# Sensor.net
KiCad netlist of a schematic drawn in Altium Designer
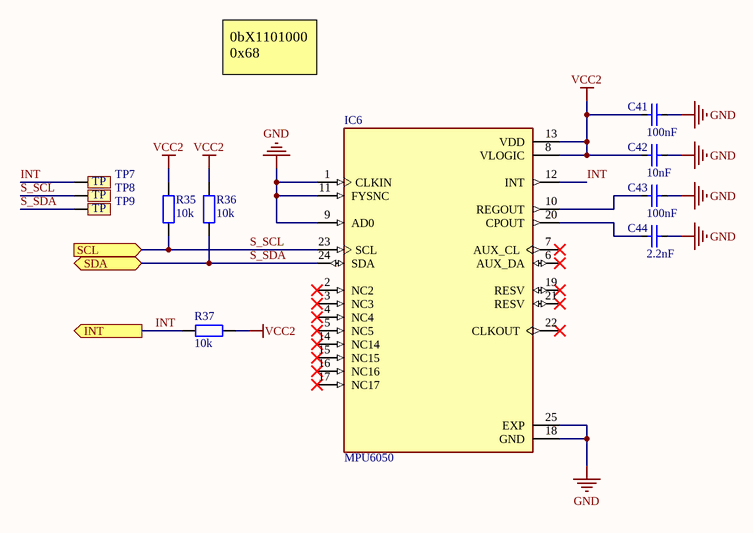
[diagram p0: Sensor.SchDoc]

(export (version "E")
  (design (tool "Eeschema 10.0.6"))
  (components
    (comp (ref "C41")
      (value "100nF")
      (footprint "CAP_0603")
      (description "Capacitor")
      (fields (field (name "PUBLISHER") "Altium Limited"))
      (libsource (lib "My Library") (part "CapSMD"))
    )
    (comp (ref "C42")
      (value "10nF")
      (footprint "CAP_0603")
      (description "Capacitor")
      (fields (field (name "PUBLISHER") "Altium Limited"))
      (libsource (lib "My Library") (part "CapSMD"))
    )
    (comp (ref "C43")
      (value "100nF")
      (footprint "CAP_0603")
      (description "Capacitor")
      (fields (field (name "PUBLISHER") "Altium Limited"))
      (libsource (lib "My Library") (part "CapSMD"))
    )
    (comp (ref "C44")
      (value "2.2nF")
      (footprint "CAP_0603")
      (description "Capacitor")
      (fields (field (name "PUBLISHER") "Altium Limited"))
      (libsource (lib "My Library") (part "CapSMD"))
    )
    (comp (ref "IC6")
      (value "MPU6050")
      (footprint "QFN24")
      (description "3-axis gyroscope, 3-axis accelerometer")
      (libsource (lib "My Library") (part "MPU6050_Chip"))
    )
    (comp (ref "R35")
      (value "10k")
      (footprint "RES-SMD-0603")
      (description "Resistor SMD")
      (fields
        (field (name "MANUFACTURER") "Generic Components")
        (field (name "PUBLISHER") "Altium Hobart Technology Centre")
      )
      (libsource (lib "My Library") (part "Resistor - SMD"))
    )
    (comp (ref "R36")
      (value "10k")
      (footprint "RES-SMD-0603")
      (description "Resistor SMD")
      (fields
        (field (name "MANUFACTURER") "Generic Components")
        (field (name "PUBLISHER") "Altium Hobart Technology Centre")
      )
      (libsource (lib "My Library") (part "Resistor - SMD"))
    )
    (comp (ref "R37")
      (value "10k")
      (footprint "RES-SMD-0603")
      (description "Resistor SMD")
      (fields
        (field (name "MANUFACTURER") "Generic Components")
        (field (name "PUBLISHER") "Altium Hobart Technology Centre")
      )
      (libsource (lib "My Library") (part "Resistor - SMD"))
    )
    (comp (ref "TP7")
      (value "TP")
      (footprint "TP_SMD")
      (description "CONNECT 1")
      (libsource (lib "My Library") (part "TP"))
    )
    (comp (ref "TP8")
      (value "TP")
      (footprint "TP_SMD")
      (description "CONNECT 1")
      (libsource (lib "My Library") (part "TP"))
    )
    (comp (ref "TP9")
      (value "TP")
      (footprint "TP_SMD")
      (description "CONNECT 1")
      (libsource (lib "My Library") (part "TP"))
    )
  )
  (nets
    (net (code "1") (name "/INT") (class "Default")
      (node (ref "IC6") (pin "12") (pinfunction "INT_12") (pintype "output"))
      (node (ref "R37") (pin "2") (pinfunction "2_2") (pintype "passive"))
      (node (ref "TP7") (pin "1") (pinfunction "0_1") (pintype "passive"))
    )
    (net (code "2") (name "/S_SCL") (class "Default")
      (node (ref "IC6") (pin "23") (pinfunction "SCL_23") (pintype "input"))
      (node (ref "R35") (pin "1") (pinfunction "1_1") (pintype "passive"))
      (node (ref "TP8") (pin "1") (pinfunction "0_1") (pintype "passive"))
    )
    (net (code "3") (name "/S_SDA") (class "Default")
      (node (ref "IC6") (pin "24") (pinfunction "SDA_24") (pintype "bidirectional"))
      (node (ref "R36") (pin "1") (pinfunction "1_1") (pintype "passive"))
      (node (ref "TP9") (pin "1") (pinfunction "0_1") (pintype "passive"))
    )
    (net (code "4") (name "GND") (class "Default")
      (node (ref "C41") (pin "1") (pinfunction "1_1") (pintype "passive"))
      (node (ref "C42") (pin "1") (pinfunction "1_1") (pintype "passive"))
      (node (ref "C43") (pin "1") (pinfunction "1_1") (pintype "passive"))
      (node (ref "C44") (pin "1") (pinfunction "1_1") (pintype "passive"))
      (node (ref "IC6") (pin "1") (pinfunction "CLKIN_1") (pintype "input"))
      (node (ref "IC6") (pin "11") (pinfunction "FYSNC_11") (pintype "input"))
      (node (ref "IC6") (pin "18") (pinfunction "GND_18") (pintype "power_in"))
      (node (ref "IC6") (pin "25") (pinfunction "EXP_25") (pintype "power_in"))
      (node (ref "IC6") (pin "9") (pinfunction "AD0_9") (pintype "input"))
    )
    (net (code "5") (name "Net-(IC6-CPOUT)") (class "Default")
      (node (ref "C44") (pin "2") (pinfunction "2_2") (pintype "passive"))
      (node (ref "IC6") (pin "20") (pinfunction "CPOUT_20") (pintype "output"))
    )
    (net (code "6") (name "Net-(IC6-REGOUT)") (class "Default")
      (node (ref "C43") (pin "2") (pinfunction "2_2") (pintype "passive"))
      (node (ref "IC6") (pin "10") (pinfunction "REGOUT_10") (pintype "output"))
    )
    (net (code "7") (name "VCC2") (class "Default")
      (node (ref "C41") (pin "2") (pinfunction "2_2") (pintype "passive"))
      (node (ref "C42") (pin "2") (pinfunction "2_2") (pintype "passive"))
      (node (ref "IC6") (pin "13") (pinfunction "VDD_13") (pintype "power_in"))
      (node (ref "IC6") (pin "8") (pinfunction "VLOGIC_8") (pintype "power_in"))
      (node (ref "R35") (pin "2") (pinfunction "2_2") (pintype "passive"))
      (node (ref "R36") (pin "2") (pinfunction "2_2") (pintype "passive"))
      (node (ref "R37") (pin "1") (pinfunction "1_1") (pintype "passive"))
    )
    (net (code "8") (name "unconnected-(IC6-AUX_CL-Pad7)") (class "Default")
      (node (ref "IC6") (pin "7") (pinfunction "AUX_CL_7") (pintype "output+no_connect"))
    )
    (net (code "9") (name "unconnected-(IC6-AUX_DA-Pad6)") (class "Default")
      (node (ref "IC6") (pin "6") (pinfunction "AUX_DA_6") (pintype "bidirectional+no_connect"))
    )
    (net (code "10") (name "unconnected-(IC6-CLKOUT-Pad22)") (class "Default")
      (node (ref "IC6") (pin "22") (pinfunction "CLKOUT_22") (pintype "output+no_connect"))
    )
    (net (code "11") (name "unconnected-(IC6-NC2-Pad2)") (class "Default")
      (node (ref "IC6") (pin "2") (pinfunction "NC2_2") (pintype "input+no_connect"))
    )
    (net (code "12") (name "unconnected-(IC6-NC3-Pad3)") (class "Default")
      (node (ref "IC6") (pin "3") (pinfunction "NC3_3") (pintype "input+no_connect"))
    )
    (net (code "13") (name "unconnected-(IC6-NC4-Pad4)") (class "Default")
      (node (ref "IC6") (pin "4") (pinfunction "NC4_4") (pintype "input+no_connect"))
    )
    (net (code "14") (name "unconnected-(IC6-NC5-Pad5)") (class "Default")
      (node (ref "IC6") (pin "5") (pinfunction "NC5_5") (pintype "input+no_connect"))
    )
    (net (code "15") (name "unconnected-(IC6-NC14-Pad14)") (class "Default")
      (node (ref "IC6") (pin "14") (pinfunction "NC14_14") (pintype "input+no_connect"))
    )
    (net (code "16") (name "unconnected-(IC6-NC15-Pad15)") (class "Default")
      (node (ref "IC6") (pin "15") (pinfunction "NC15_15") (pintype "input+no_connect"))
    )
    (net (code "17") (name "unconnected-(IC6-NC16-Pad16)") (class "Default")
      (node (ref "IC6") (pin "16") (pinfunction "NC16_16") (pintype "input+no_connect"))
    )
    (net (code "18") (name "unconnected-(IC6-NC17-Pad17)") (class "Default")
      (node (ref "IC6") (pin "17") (pinfunction "NC17_17") (pintype "input+no_connect"))
    )
    (net (code "19") (name "unconnected-(IC6-RESV-Pad19)") (class "Default")
      (node (ref "IC6") (pin "19") (pinfunction "RESV_19") (pintype "bidirectional+no_connect"))
    )
    (net (code "20") (name "unconnected-(IC6-RESV-Pad21)") (class "Default")
      (node (ref "IC6") (pin "21") (pinfunction "RESV_21") (pintype "bidirectional+no_connect"))
    )
  )
)
